# cubey_v3.net
KiCad netlist of a schematic drawn in EAGLE
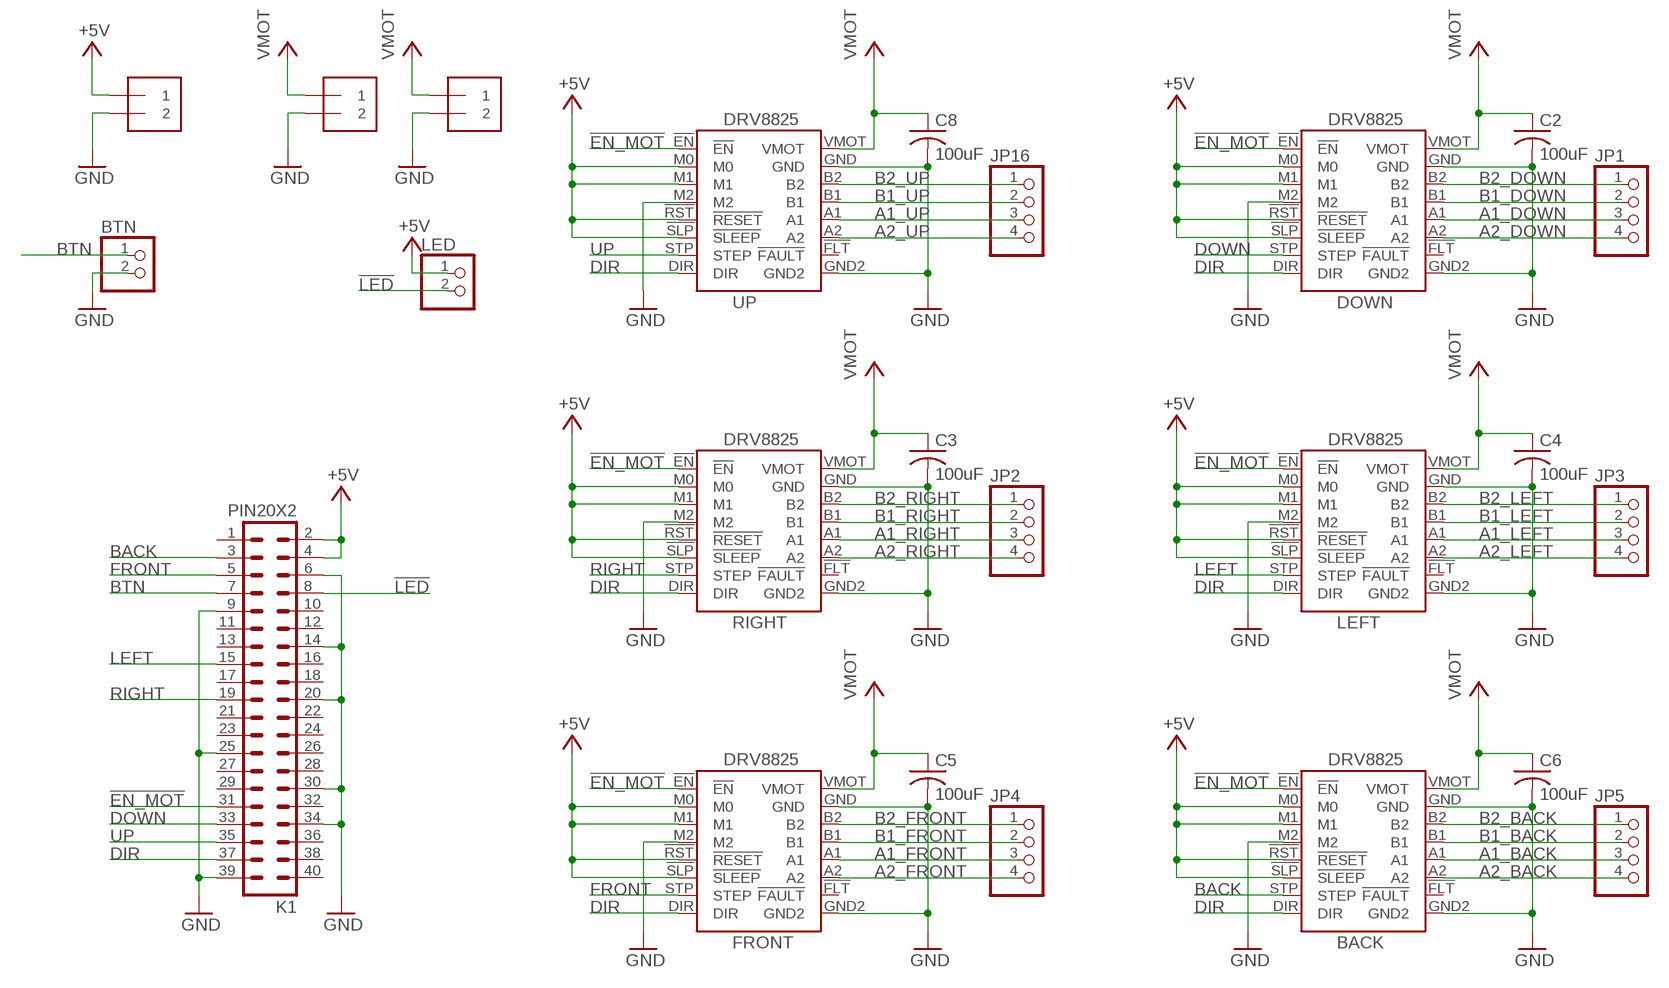
[diagram p0: schematic, sheet 1]

(export (version "E")
  (design (tool "Eeschema 10.0.6"))
  (components
    (comp (ref "5V_PWR")
      (value "1X2-3.5MM")
      (footprint "eagle-import:1X2-3.5MM")
      (libsource (lib "eagle-import") (part "1X2-3.5MM"))
    )
    (comp (ref "BACK")
      (value "DRV_8825_SOCKET")
      (footprint "eagle-import:DRV_8825_DIP")
      (libsource (lib "eagle-import") (part "DRV_8825_SOCKET"))
    )
    (comp (ref "BTN")
      (value "PINHD-1X2")
      (footprint "eagle-import:1X02")
      (libsource (lib "eagle-import") (part "PINHD-1X2"))
    )
    (comp (ref "C2")
      (value "100uF")
      (footprint "eagle-import:C025-025X050")
      (libsource (lib "eagle-import") (part "C-US025-025X050"))
    )
    (comp (ref "C3")
      (value "100uF")
      (footprint "eagle-import:C025-025X050")
      (libsource (lib "eagle-import") (part "C-US025-025X050"))
    )
    (comp (ref "C4")
      (value "100uF")
      (footprint "eagle-import:C025-025X050")
      (libsource (lib "eagle-import") (part "C-US025-025X050"))
    )
    (comp (ref "C5")
      (value "100uF")
      (footprint "eagle-import:C025-025X050")
      (libsource (lib "eagle-import") (part "C-US025-025X050"))
    )
    (comp (ref "C6")
      (value "100uF")
      (footprint "eagle-import:C025-025X050")
      (libsource (lib "eagle-import") (part "C-US025-025X050"))
    )
    (comp (ref "C8")
      (value "100uF")
      (footprint "eagle-import:C025-025X050")
      (libsource (lib "eagle-import") (part "C-US025-025X050"))
    )
    (comp (ref "DOWN")
      (value "DRV_8825_SOCKET")
      (footprint "eagle-import:DRV_8825_DIP")
      (libsource (lib "eagle-import") (part "DRV_8825_SOCKET"))
    )
    (comp (ref "FRONT")
      (value "DRV_8825_SOCKET")
      (footprint "eagle-import:DRV_8825_DIP")
      (libsource (lib "eagle-import") (part "DRV_8825_SOCKET"))
    )
    (comp (ref "JP1")
      (value "PINHD-1X4")
      (footprint "eagle-import:1X04")
      (libsource (lib "eagle-import") (part "PINHD-1X4"))
    )
    (comp (ref "JP2")
      (value "PINHD-1X4")
      (footprint "eagle-import:1X04")
      (libsource (lib "eagle-import") (part "PINHD-1X4"))
    )
    (comp (ref "JP3")
      (value "PINHD-1X4")
      (footprint "eagle-import:1X04")
      (libsource (lib "eagle-import") (part "PINHD-1X4"))
    )
    (comp (ref "JP4")
      (value "PINHD-1X4")
      (footprint "eagle-import:1X04")
      (libsource (lib "eagle-import") (part "PINHD-1X4"))
    )
    (comp (ref "JP5")
      (value "PINHD-1X4")
      (footprint "eagle-import:1X04")
      (libsource (lib "eagle-import") (part "PINHD-1X4"))
    )
    (comp (ref "JP16")
      (value "PINHD-1X4")
      (footprint "eagle-import:1X04")
      (libsource (lib "eagle-import") (part "PINHD-1X4"))
    )
    (comp (ref "K1")
      (value "PIN20X2")
      (footprint "eagle-import:PIN_20X2")
      (libsource (lib "eagle-import") (part "PIN20X2"))
    )
    (comp (ref "LED")
      (value "PINHD-1X2")
      (footprint "eagle-import:1X02")
      (libsource (lib "eagle-import") (part "PINHD-1X2"))
    )
    (comp (ref "LEFT")
      (value "DRV_8825_SOCKET")
      (footprint "eagle-import:DRV_8825_DIP")
      (libsource (lib "eagle-import") (part "DRV_8825_SOCKET"))
    )
    (comp (ref "MOT_PWR")
      (value "1X2-3.5MM")
      (footprint "eagle-import:1X2-3.5MM")
      (libsource (lib "eagle-import") (part "1X2-3.5MM"))
    )
    (comp (ref "MOT_PWR1")
      (value "1X2-3.5MM")
      (footprint "eagle-import:1X2-3.5MM")
      (libsource (lib "eagle-import") (part "1X2-3.5MM"))
    )
    (comp (ref "RIGHT")
      (value "DRV_8825_SOCKET")
      (footprint "eagle-import:DRV_8825_DIP")
      (libsource (lib "eagle-import") (part "DRV_8825_SOCKET"))
    )
    (comp (ref "UP")
      (value "DRV_8825_SOCKET")
      (footprint "eagle-import:DRV_8825_DIP")
      (libsource (lib "eagle-import") (part "DRV_8825_SOCKET"))
    )
  )
  (nets
    (net (code "1") (name "+5V") (class "Default")
      (node (ref "5V_PWR") (pin "1") (pinfunction "1_1") (pintype "passive"))
      (node (ref "BACK") (pin "!RST") (pinfunction "~{RESET}_!RST") (pintype "bidirectional"))
      (node (ref "BACK") (pin "!SLP") (pinfunction "~{SLEEP}_!SLP") (pintype "bidirectional"))
      (node (ref "BACK") (pin "M0") (pinfunction "M0_M0") (pintype "bidirectional"))
      (node (ref "BACK") (pin "M1") (pinfunction "M1_M1") (pintype "bidirectional"))
      (node (ref "DOWN") (pin "!RST") (pinfunction "~{RESET}_!RST") (pintype "bidirectional"))
      (node (ref "DOWN") (pin "!SLP") (pinfunction "~{SLEEP}_!SLP") (pintype "bidirectional"))
      (node (ref "DOWN") (pin "M0") (pinfunction "M0_M0") (pintype "bidirectional"))
      (node (ref "DOWN") (pin "M1") (pinfunction "M1_M1") (pintype "bidirectional"))
      (node (ref "FRONT") (pin "!RST") (pinfunction "~{RESET}_!RST") (pintype "bidirectional"))
      (node (ref "FRONT") (pin "!SLP") (pinfunction "~{SLEEP}_!SLP") (pintype "bidirectional"))
      (node (ref "FRONT") (pin "M0") (pinfunction "M0_M0") (pintype "bidirectional"))
      (node (ref "FRONT") (pin "M1") (pinfunction "M1_M1") (pintype "bidirectional"))
      (node (ref "K1") (pin "2") (pinfunction "2_2") (pintype "passive"))
      (node (ref "K1") (pin "4") (pinfunction "4_4") (pintype "passive"))
      (node (ref "LED") (pin "1") (pinfunction "1_1") (pintype "passive"))
      (node (ref "LEFT") (pin "!RST") (pinfunction "~{RESET}_!RST") (pintype "bidirectional"))
      (node (ref "LEFT") (pin "!SLP") (pinfunction "~{SLEEP}_!SLP") (pintype "bidirectional"))
      (node (ref "LEFT") (pin "M0") (pinfunction "M0_M0") (pintype "bidirectional"))
      (node (ref "LEFT") (pin "M1") (pinfunction "M1_M1") (pintype "bidirectional"))
      (node (ref "RIGHT") (pin "!RST") (pinfunction "~{RESET}_!RST") (pintype "bidirectional"))
      (node (ref "RIGHT") (pin "!SLP") (pinfunction "~{SLEEP}_!SLP") (pintype "bidirectional"))
      (node (ref "RIGHT") (pin "M0") (pinfunction "M0_M0") (pintype "bidirectional"))
      (node (ref "RIGHT") (pin "M1") (pinfunction "M1_M1") (pintype "bidirectional"))
      (node (ref "UP") (pin "!RST") (pinfunction "~{RESET}_!RST") (pintype "bidirectional"))
      (node (ref "UP") (pin "!SLP") (pinfunction "~{SLEEP}_!SLP") (pintype "bidirectional"))
      (node (ref "UP") (pin "M0") (pinfunction "M0_M0") (pintype "bidirectional"))
      (node (ref "UP") (pin "M1") (pinfunction "M1_M1") (pintype "bidirectional"))
    )
    (net (code "2") (name "/A1_BACK") (class "Default")
      (node (ref "BACK") (pin "A1") (pinfunction "A1_A1") (pintype "power_in"))
      (node (ref "JP5") (pin "3") (pinfunction "3_3") (pintype "passive"))
    )
    (net (code "3") (name "/A1_DOWN") (class "Default")
      (node (ref "DOWN") (pin "A1") (pinfunction "A1_A1") (pintype "power_in"))
      (node (ref "JP1") (pin "3") (pinfunction "3_3") (pintype "passive"))
    )
    (net (code "4") (name "/A1_FRONT") (class "Default")
      (node (ref "FRONT") (pin "A1") (pinfunction "A1_A1") (pintype "power_in"))
      (node (ref "JP4") (pin "3") (pinfunction "3_3") (pintype "passive"))
    )
    (net (code "5") (name "/A1_LEFT") (class "Default")
      (node (ref "JP3") (pin "3") (pinfunction "3_3") (pintype "passive"))
      (node (ref "LEFT") (pin "A1") (pinfunction "A1_A1") (pintype "power_in"))
    )
    (net (code "6") (name "/A1_RIGHT") (class "Default")
      (node (ref "JP2") (pin "3") (pinfunction "3_3") (pintype "passive"))
      (node (ref "RIGHT") (pin "A1") (pinfunction "A1_A1") (pintype "power_in"))
    )
    (net (code "7") (name "/A1_UP") (class "Default")
      (node (ref "JP16") (pin "3") (pinfunction "3_3") (pintype "passive"))
      (node (ref "UP") (pin "A1") (pinfunction "A1_A1") (pintype "power_in"))
    )
    (net (code "8") (name "/A2_BACK") (class "Default")
      (node (ref "BACK") (pin "A2") (pinfunction "A2_A2") (pintype "power_in"))
      (node (ref "JP5") (pin "4") (pinfunction "4_4") (pintype "passive"))
    )
    (net (code "9") (name "/A2_DOWN") (class "Default")
      (node (ref "DOWN") (pin "A2") (pinfunction "A2_A2") (pintype "power_in"))
      (node (ref "JP1") (pin "4") (pinfunction "4_4") (pintype "passive"))
    )
    (net (code "10") (name "/A2_FRONT") (class "Default")
      (node (ref "FRONT") (pin "A2") (pinfunction "A2_A2") (pintype "power_in"))
      (node (ref "JP4") (pin "4") (pinfunction "4_4") (pintype "passive"))
    )
    (net (code "11") (name "/A2_LEFT") (class "Default")
      (node (ref "JP3") (pin "4") (pinfunction "4_4") (pintype "passive"))
      (node (ref "LEFT") (pin "A2") (pinfunction "A2_A2") (pintype "power_in"))
    )
    (net (code "12") (name "/A2_RIGHT") (class "Default")
      (node (ref "JP2") (pin "4") (pinfunction "4_4") (pintype "passive"))
      (node (ref "RIGHT") (pin "A2") (pinfunction "A2_A2") (pintype "power_in"))
    )
    (net (code "13") (name "/A2_UP") (class "Default")
      (node (ref "JP16") (pin "4") (pinfunction "4_4") (pintype "passive"))
      (node (ref "UP") (pin "A2") (pinfunction "A2_A2") (pintype "power_in"))
    )
    (net (code "14") (name "/B1_BACK") (class "Default")
      (node (ref "BACK") (pin "B1") (pinfunction "B1_B1") (pintype "power_in"))
      (node (ref "JP5") (pin "2") (pinfunction "2_2") (pintype "passive"))
    )
    (net (code "15") (name "/B1_DOWN") (class "Default")
      (node (ref "DOWN") (pin "B1") (pinfunction "B1_B1") (pintype "power_in"))
      (node (ref "JP1") (pin "2") (pinfunction "2_2") (pintype "passive"))
    )
    (net (code "16") (name "/B1_FRONT") (class "Default")
      (node (ref "FRONT") (pin "B1") (pinfunction "B1_B1") (pintype "power_in"))
      (node (ref "JP4") (pin "2") (pinfunction "2_2") (pintype "passive"))
    )
    (net (code "17") (name "/B1_LEFT") (class "Default")
      (node (ref "JP3") (pin "2") (pinfunction "2_2") (pintype "passive"))
      (node (ref "LEFT") (pin "B1") (pinfunction "B1_B1") (pintype "power_in"))
    )
    (net (code "18") (name "/B1_RIGHT") (class "Default")
      (node (ref "JP2") (pin "2") (pinfunction "2_2") (pintype "passive"))
      (node (ref "RIGHT") (pin "B1") (pinfunction "B1_B1") (pintype "power_in"))
    )
    (net (code "19") (name "/B1_UP") (class "Default")
      (node (ref "JP16") (pin "2") (pinfunction "2_2") (pintype "passive"))
      (node (ref "UP") (pin "B1") (pinfunction "B1_B1") (pintype "power_in"))
    )
    (net (code "20") (name "/B2_BACK") (class "Default")
      (node (ref "BACK") (pin "B2") (pinfunction "B2_B2") (pintype "power_in"))
      (node (ref "JP5") (pin "1") (pinfunction "1_1") (pintype "passive"))
    )
    (net (code "21") (name "/B2_DOWN") (class "Default")
      (node (ref "DOWN") (pin "B2") (pinfunction "B2_B2") (pintype "power_in"))
      (node (ref "JP1") (pin "1") (pinfunction "1_1") (pintype "passive"))
    )
    (net (code "22") (name "/B2_FRONT") (class "Default")
      (node (ref "FRONT") (pin "B2") (pinfunction "B2_B2") (pintype "power_in"))
      (node (ref "JP4") (pin "1") (pinfunction "1_1") (pintype "passive"))
    )
    (net (code "23") (name "/B2_LEFT") (class "Default")
      (node (ref "JP3") (pin "1") (pinfunction "1_1") (pintype "passive"))
      (node (ref "LEFT") (pin "B2") (pinfunction "B2_B2") (pintype "power_in"))
    )
    (net (code "24") (name "/B2_RIGHT") (class "Default")
      (node (ref "JP2") (pin "1") (pinfunction "1_1") (pintype "passive"))
      (node (ref "RIGHT") (pin "B2") (pinfunction "B2_B2") (pintype "power_in"))
    )
    (net (code "25") (name "/B2_UP") (class "Default")
      (node (ref "JP16") (pin "1") (pinfunction "1_1") (pintype "passive"))
      (node (ref "UP") (pin "B2") (pinfunction "B2_B2") (pintype "power_in"))
    )
    (net (code "26") (name "/BACK") (class "Default")
      (node (ref "BACK") (pin "STP") (pinfunction "STEP_STP") (pintype "bidirectional"))
      (node (ref "K1") (pin "3") (pinfunction "3_3") (pintype "passive"))
    )
    (net (code "27") (name "/BTN") (class "Default")
      (node (ref "BTN") (pin "1") (pinfunction "1_1") (pintype "passive"))
      (node (ref "K1") (pin "7") (pinfunction "7_7") (pintype "passive"))
    )
    (net (code "28") (name "/DIR") (class "Default")
      (node (ref "BACK") (pin "DIR") (pinfunction "DIR_DIR") (pintype "bidirectional"))
      (node (ref "DOWN") (pin "DIR") (pinfunction "DIR_DIR") (pintype "bidirectional"))
      (node (ref "FRONT") (pin "DIR") (pinfunction "DIR_DIR") (pintype "bidirectional"))
      (node (ref "K1") (pin "37") (pinfunction "37_37") (pintype "passive"))
      (node (ref "LEFT") (pin "DIR") (pinfunction "DIR_DIR") (pintype "bidirectional"))
      (node (ref "RIGHT") (pin "DIR") (pinfunction "DIR_DIR") (pintype "bidirectional"))
      (node (ref "UP") (pin "DIR") (pinfunction "DIR_DIR") (pintype "bidirectional"))
    )
    (net (code "29") (name "/DOWN") (class "Default")
      (node (ref "DOWN") (pin "STP") (pinfunction "STEP_STP") (pintype "bidirectional"))
      (node (ref "K1") (pin "33") (pinfunction "33_33") (pintype "passive"))
    )
    (net (code "30") (name "/FRONT") (class "Default")
      (node (ref "FRONT") (pin "STP") (pinfunction "STEP_STP") (pintype "bidirectional"))
      (node (ref "K1") (pin "5") (pinfunction "5_5") (pintype "passive"))
    )
    (net (code "31") (name "/LEFT") (class "Default")
      (node (ref "K1") (pin "15") (pinfunction "15_15") (pintype "passive"))
      (node (ref "LEFT") (pin "STP") (pinfunction "STEP_STP") (pintype "bidirectional"))
    )
    (net (code "32") (name "/RIGHT") (class "Default")
      (node (ref "K1") (pin "19") (pinfunction "19_19") (pintype "passive"))
      (node (ref "RIGHT") (pin "STP") (pinfunction "STEP_STP") (pintype "bidirectional"))
    )
    (net (code "33") (name "/UP") (class "Default")
      (node (ref "K1") (pin "35") (pinfunction "35_35") (pintype "passive"))
      (node (ref "UP") (pin "STP") (pinfunction "STEP_STP") (pintype "bidirectional"))
    )
    (net (code "34") (name "/~{EN_MOT}") (class "Default")
      (node (ref "BACK") (pin "!EN") (pinfunction "~{EN}_!EN") (pintype "bidirectional"))
      (node (ref "DOWN") (pin "!EN") (pinfunction "~{EN}_!EN") (pintype "bidirectional"))
      (node (ref "FRONT") (pin "!EN") (pinfunction "~{EN}_!EN") (pintype "bidirectional"))
      (node (ref "K1") (pin "31") (pinfunction "31_31") (pintype "passive"))
      (node (ref "LEFT") (pin "!EN") (pinfunction "~{EN}_!EN") (pintype "bidirectional"))
      (node (ref "RIGHT") (pin "!EN") (pinfunction "~{EN}_!EN") (pintype "bidirectional"))
      (node (ref "UP") (pin "!EN") (pinfunction "~{EN}_!EN") (pintype "bidirectional"))
    )
    (net (code "35") (name "/~{LED}") (class "Default")
      (node (ref "K1") (pin "8") (pinfunction "8_8") (pintype "passive"))
      (node (ref "LED") (pin "2") (pinfunction "2_2") (pintype "passive"))
    )
    (net (code "36") (name "GND") (class "Default")
      (node (ref "5V_PWR") (pin "2") (pinfunction "2_2") (pintype "passive"))
      (node (ref "BACK") (pin "GND") (pinfunction "GND_GND") (pintype "power_in"))
      (node (ref "BACK") (pin "GND2") (pinfunction "GND2_GND2") (pintype "power_in"))
      (node (ref "BACK") (pin "M2") (pinfunction "M2_M2") (pintype "bidirectional"))
      (node (ref "BTN") (pin "2") (pinfunction "2_2") (pintype "passive"))
      (node (ref "C2") (pin "2") (pinfunction "2_2") (pintype "passive"))
      (node (ref "C3") (pin "2") (pinfunction "2_2") (pintype "passive"))
      (node (ref "C4") (pin "2") (pinfunction "2_2") (pintype "passive"))
      (node (ref "C5") (pin "2") (pinfunction "2_2") (pintype "passive"))
      (node (ref "C6") (pin "2") (pinfunction "2_2") (pintype "passive"))
      (node (ref "C8") (pin "2") (pinfunction "2_2") (pintype "passive"))
      (node (ref "DOWN") (pin "GND") (pinfunction "GND_GND") (pintype "power_in"))
      (node (ref "DOWN") (pin "GND2") (pinfunction "GND2_GND2") (pintype "power_in"))
      (node (ref "DOWN") (pin "M2") (pinfunction "M2_M2") (pintype "bidirectional"))
      (node (ref "FRONT") (pin "GND") (pinfunction "GND_GND") (pintype "power_in"))
      (node (ref "FRONT") (pin "GND2") (pinfunction "GND2_GND2") (pintype "power_in"))
      (node (ref "FRONT") (pin "M2") (pinfunction "M2_M2") (pintype "bidirectional"))
      (node (ref "K1") (pin "14") (pinfunction "14_14") (pintype "passive"))
      (node (ref "K1") (pin "20") (pinfunction "20_20") (pintype "passive"))
      (node (ref "K1") (pin "25") (pinfunction "25_25") (pintype "passive"))
      (node (ref "K1") (pin "30") (pinfunction "30_30") (pintype "passive"))
      (node (ref "K1") (pin "34") (pinfunction "34_34") (pintype "passive"))
      (node (ref "K1") (pin "39") (pinfunction "39_39") (pintype "passive"))
      (node (ref "K1") (pin "6") (pinfunction "6_6") (pintype "passive"))
      (node (ref "K1") (pin "9") (pinfunction "9_9") (pintype "passive"))
      (node (ref "LEFT") (pin "GND") (pinfunction "GND_GND") (pintype "power_in"))
      (node (ref "LEFT") (pin "GND2") (pinfunction "GND2_GND2") (pintype "power_in"))
      (node (ref "LEFT") (pin "M2") (pinfunction "M2_M2") (pintype "bidirectional"))
      (node (ref "MOT_PWR") (pin "2") (pinfunction "2_2") (pintype "passive"))
      (node (ref "MOT_PWR1") (pin "2") (pinfunction "2_2") (pintype "passive"))
      (node (ref "RIGHT") (pin "GND") (pinfunction "GND_GND") (pintype "power_in"))
      (node (ref "RIGHT") (pin "GND2") (pinfunction "GND2_GND2") (pintype "power_in"))
      (node (ref "RIGHT") (pin "M2") (pinfunction "M2_M2") (pintype "bidirectional"))
      (node (ref "UP") (pin "GND") (pinfunction "GND_GND") (pintype "power_in"))
      (node (ref "UP") (pin "GND2") (pinfunction "GND2_GND2") (pintype "power_in"))
      (node (ref "UP") (pin "M2") (pinfunction "M2_M2") (pintype "bidirectional"))
    )
    (net (code "37") (name "VMOT") (class "Default")
      (node (ref "BACK") (pin "VMOT") (pinfunction "VMOT_VMOT") (pintype "power_in"))
      (node (ref "C2") (pin "1") (pinfunction "1_1") (pintype "passive"))
      (node (ref "C3") (pin "1") (pinfunction "1_1") (pintype "passive"))
      (node (ref "C4") (pin "1") (pinfunction "1_1") (pintype "passive"))
      (node (ref "C5") (pin "1") (pinfunction "1_1") (pintype "passive"))
      (node (ref "C6") (pin "1") (pinfunction "1_1") (pintype "passive"))
      (node (ref "C8") (pin "1") (pinfunction "1_1") (pintype "passive"))
      (node (ref "DOWN") (pin "VMOT") (pinfunction "VMOT_VMOT") (pintype "power_in"))
      (node (ref "FRONT") (pin "VMOT") (pinfunction "VMOT_VMOT") (pintype "power_in"))
      (node (ref "LEFT") (pin "VMOT") (pinfunction "VMOT_VMOT") (pintype "power_in"))
      (node (ref "MOT_PWR") (pin "1") (pinfunction "1_1") (pintype "passive"))
      (node (ref "MOT_PWR1") (pin "1") (pinfunction "1_1") (pintype "passive"))
      (node (ref "RIGHT") (pin "VMOT") (pinfunction "VMOT_VMOT") (pintype "power_in"))
      (node (ref "UP") (pin "VMOT") (pinfunction "VMOT_VMOT") (pintype "power_in"))
    )
    (net (code "38") (name "unconnected-(BACK-~{FAULT}-Pad!FLT)") (class "Default")
      (node (ref "BACK") (pin "!FLT") (pinfunction "~{FAULT}_!FLT") (pintype "bidirectional"))
    )
    (net (code "39") (name "unconnected-(DOWN-~{FAULT}-Pad!FLT)") (class "Default")
      (node (ref "DOWN") (pin "!FLT") (pinfunction "~{FAULT}_!FLT") (pintype "bidirectional"))
    )
    (net (code "40") (name "unconnected-(FRONT-~{FAULT}-Pad!FLT)") (class "Default")
      (node (ref "FRONT") (pin "!FLT") (pinfunction "~{FAULT}_!FLT") (pintype "bidirectional"))
    )
    (net (code "41") (name "unconnected-(K1-Pad1)") (class "Default")
      (node (ref "K1") (pin "1") (pinfunction "1_1") (pintype "passive"))
    )
    (net (code "42") (name "unconnected-(K1-Pad10)") (class "Default")
      (node (ref "K1") (pin "10") (pinfunction "10_10") (pintype "passive"))
    )
    (net (code "43") (name "unconnected-(K1-Pad11)") (class "Default")
      (node (ref "K1") (pin "11") (pinfunction "11_11") (pintype "passive"))
    )
    (net (code "44") (name "unconnected-(K1-Pad12)") (class "Default")
      (node (ref "K1") (pin "12") (pinfunction "12_12") (pintype "passive"))
    )
    (net (code "45") (name "unconnected-(K1-Pad13)") (class "Default")
      (node (ref "K1") (pin "13") (pinfunction "13_13") (pintype "passive"))
    )
    (net (code "46") (name "unconnected-(K1-Pad16)") (class "Default")
      (node (ref "K1") (pin "16") (pinfunction "16_16") (pintype "passive"))
    )
    (net (code "47") (name "unconnected-(K1-Pad17)") (class "Default")
      (node (ref "K1") (pin "17") (pinfunction "17_17") (pintype "passive"))
    )
    (net (code "48") (name "unconnected-(K1-Pad18)") (class "Default")
      (node (ref "K1") (pin "18") (pinfunction "18_18") (pintype "passive"))
    )
    (net (code "49") (name "unconnected-(K1-Pad21)") (class "Default")
      (node (ref "K1") (pin "21") (pinfunction "21_21") (pintype "passive"))
    )
    (net (code "50") (name "unconnected-(K1-Pad22)") (class "Default")
      (node (ref "K1") (pin "22") (pinfunction "22_22") (pintype "passive"))
    )
    (net (code "51") (name "unconnected-(K1-Pad23)") (class "Default")
      (node (ref "K1") (pin "23") (pinfunction "23_23") (pintype "passive"))
    )
    (net (code "52") (name "unconnected-(K1-Pad24)") (class "Default")
      (node (ref "K1") (pin "24") (pinfunction "24_24") (pintype "passive"))
    )
    (net (code "53") (name "unconnected-(K1-Pad26)") (class "Default")
      (node (ref "K1") (pin "26") (pinfunction "26_26") (pintype "passive"))
    )
    (net (code "54") (name "unconnected-(K1-Pad27)") (class "Default")
      (node (ref "K1") (pin "27") (pinfunction "27_27") (pintype "passive"))
    )
    (net (code "55") (name "unconnected-(K1-Pad28)") (class "Default")
      (node (ref "K1") (pin "28") (pinfunction "28_28") (pintype "passive"))
    )
    (net (code "56") (name "unconnected-(K1-Pad29)") (class "Default")
      (node (ref "K1") (pin "29") (pinfunction "29_29") (pintype "passive"))
    )
    (net (code "57") (name "unconnected-(K1-Pad32)") (class "Default")
      (node (ref "K1") (pin "32") (pinfunction "32_32") (pintype "passive"))
    )
    (net (code "58") (name "unconnected-(K1-Pad36)") (class "Default")
      (node (ref "K1") (pin "36") (pinfunction "36_36") (pintype "passive"))
    )
    (net (code "59") (name "unconnected-(K1-Pad38)") (class "Default")
      (node (ref "K1") (pin "38") (pinfunction "38_38") (pintype "passive"))
    )
    (net (code "60") (name "unconnected-(K1-Pad40)") (class "Default")
      (node (ref "K1") (pin "40") (pinfunction "40_40") (pintype "passive"))
    )
    (net (code "61") (name "unconnected-(LEFT-~{FAULT}-Pad!FLT)") (class "Default")
      (node (ref "LEFT") (pin "!FLT") (pinfunction "~{FAULT}_!FLT") (pintype "bidirectional"))
    )
    (net (code "62") (name "unconnected-(RIGHT-~{FAULT}-Pad!FLT)") (class "Default")
      (node (ref "RIGHT") (pin "!FLT") (pinfunction "~{FAULT}_!FLT") (pintype "bidirectional"))
    )
    (net (code "63") (name "unconnected-(UP-~{FAULT}-Pad!FLT)") (class "Default")
      (node (ref "UP") (pin "!FLT") (pinfunction "~{FAULT}_!FLT") (pintype "bidirectional"))
    )
  )
)
